# LEDA_Arcade_Controller_Mainboard_No_Spea.net
KiCad netlist of a schematic drawn in EasyEDA
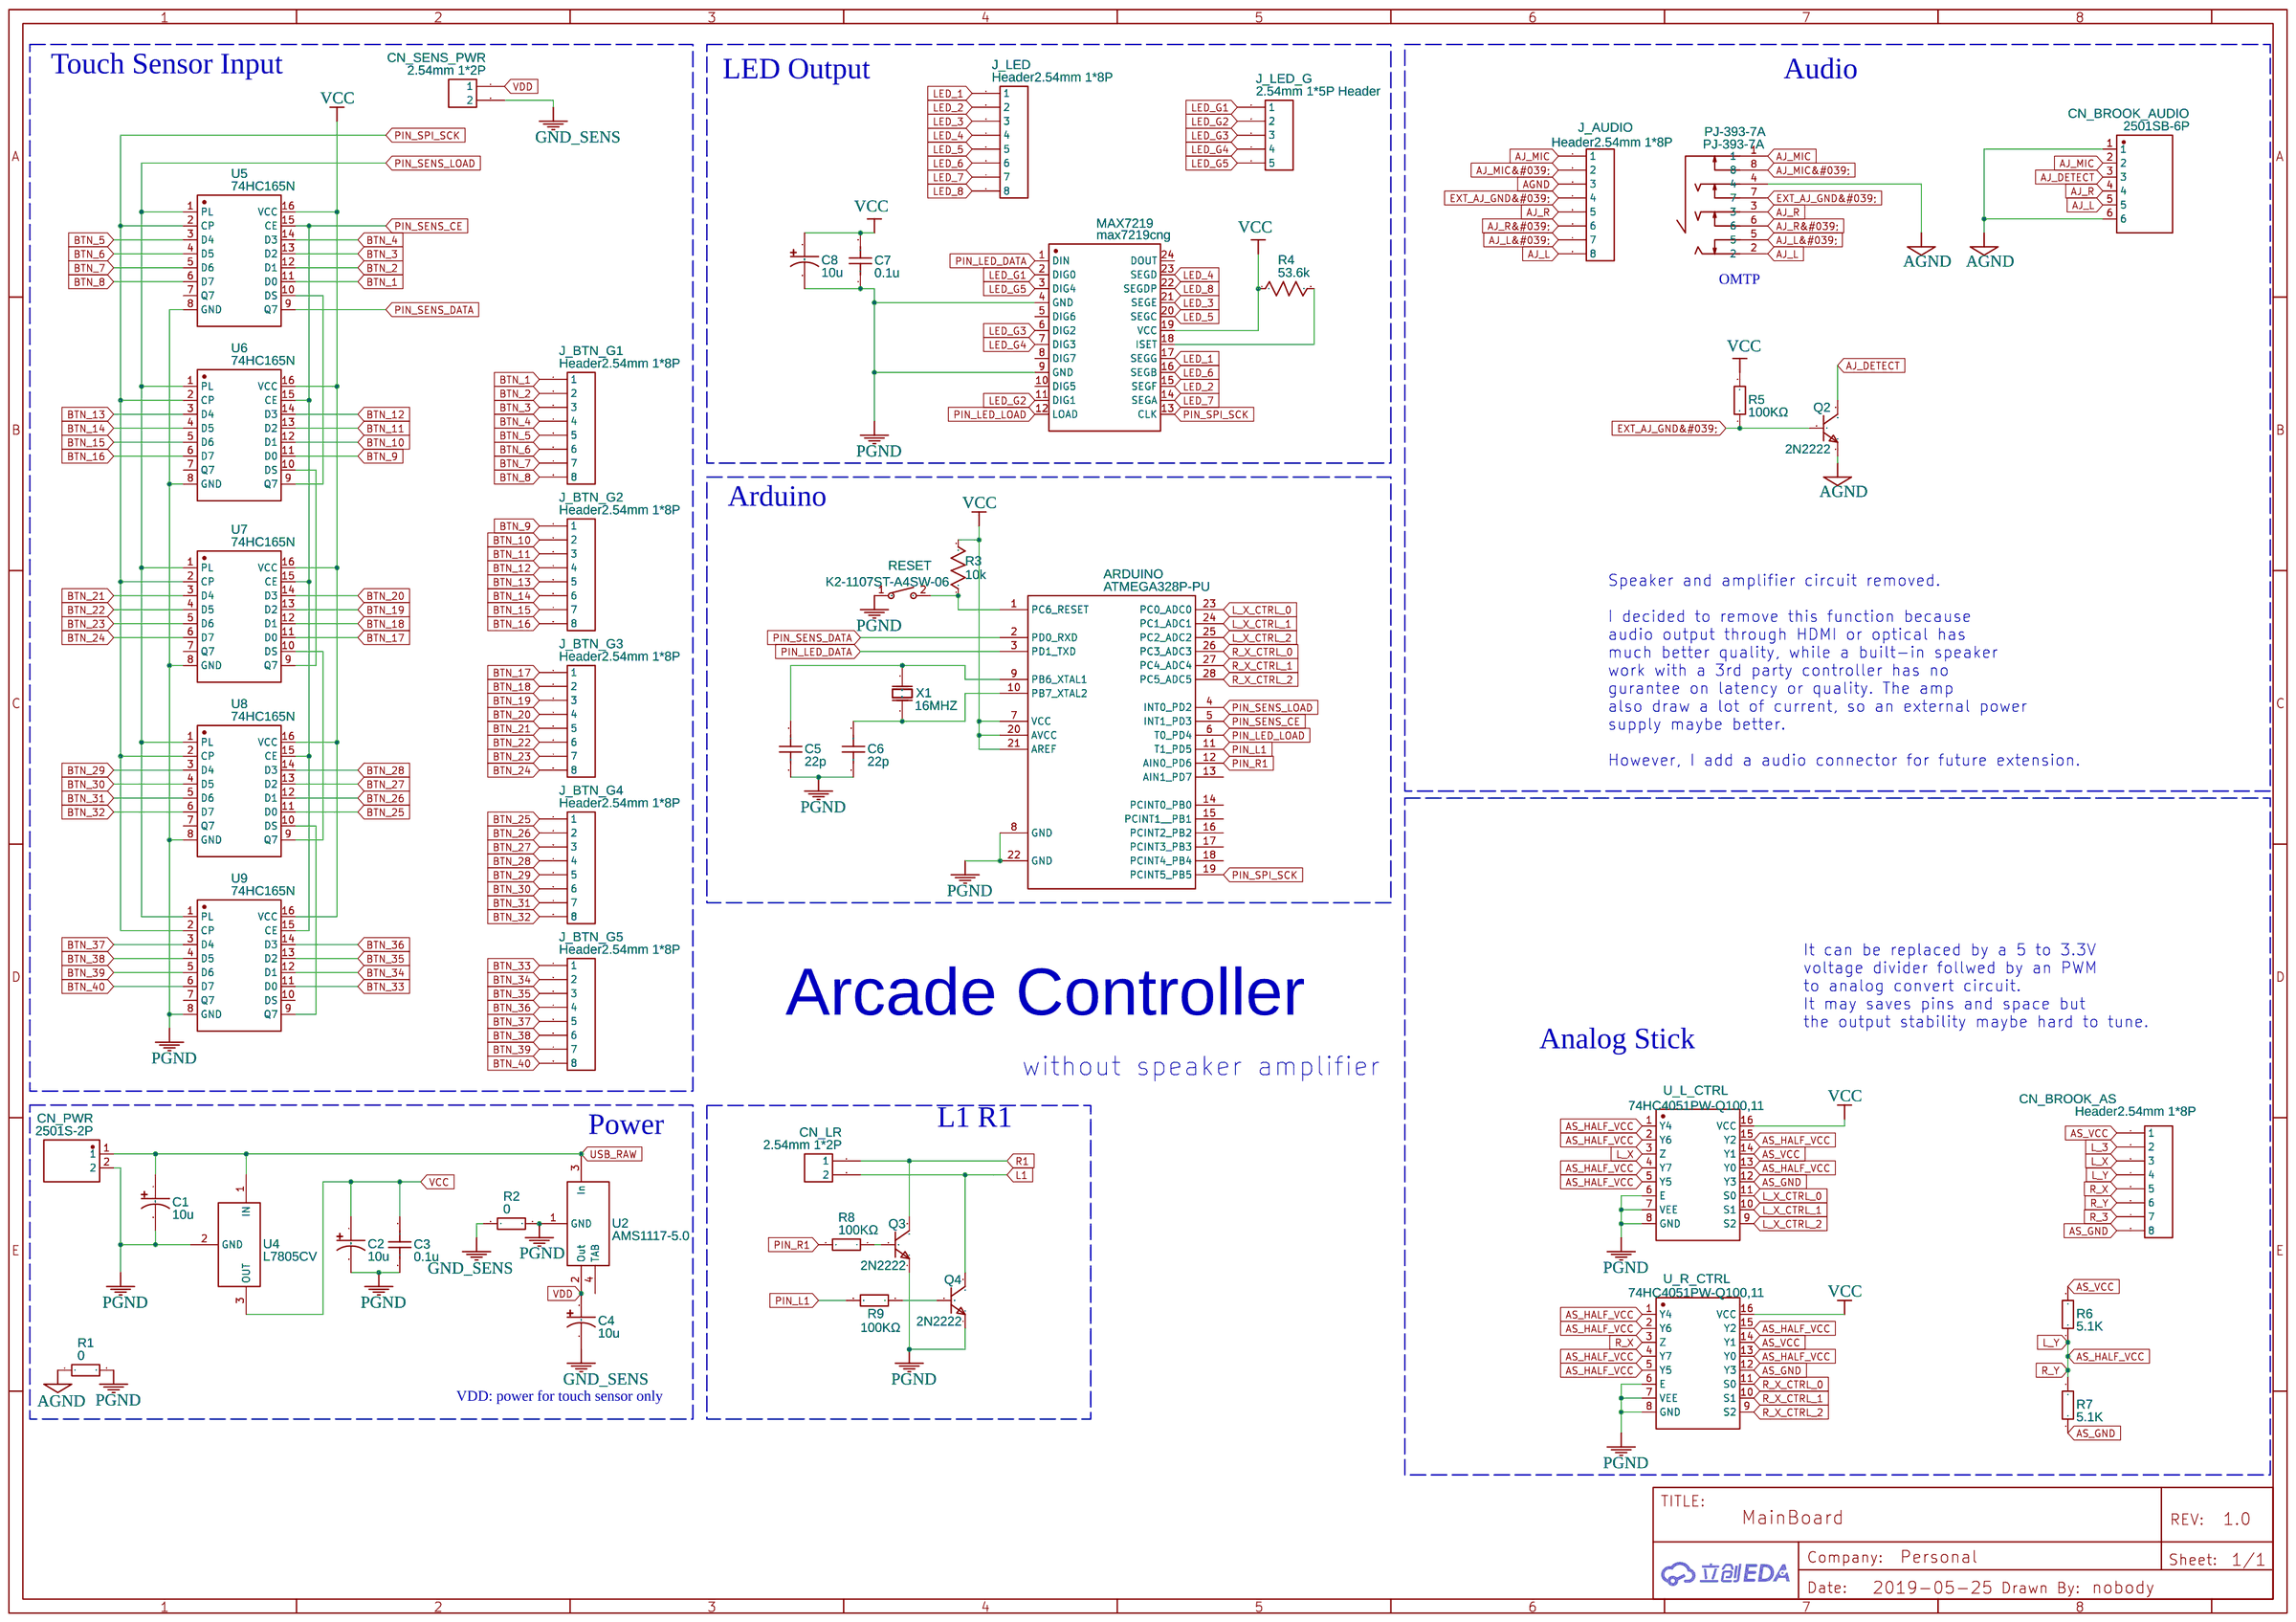
[diagram p0: schematic sheet]

(export (version "E")
  (design (tool "Eeschema 10.0.6"))
  (components
    (comp (ref "ARDUINO")
      (value "ATMEGA328P-PU")
      (fields (field (name "BOM_Supplier Part") "C33901"))
      (libsource (lib "") (part "Unknown_790_525"))
    )
    (comp (ref "C1")
      (value "10u")
      (fields (field (name "BOM_Manufacturer Part") "?"))
      (libsource (lib "") (part "Cap_Electrolytic(TH)_D4.0XF1.5_US_1"))
    )
    (comp (ref "C2")
      (value "10u")
      (fields (field (name "BOM_Manufacturer Part") "?"))
      (libsource (lib "") (part "Cap_Electrolytic(TH)_D4.0XF1.5_US_1"))
    )
    (comp (ref "C3")
      (value "0.1u")
      (fields (field (name "BOM_Manufacturer Part") "?"))
      (libsource (lib "") (part "Cap_RAD-0.2_US"))
    )
    (comp (ref "C4")
      (value "10u")
      (fields (field (name "BOM_Manufacturer Part") "?"))
      (libsource (lib "") (part "Cap_Electrolytic(TH)_D4.0XF1.5_US_2"))
    )
    (comp (ref "C5")
      (value "22p")
      (fields (field (name "BOM_Manufacturer Part") "?"))
      (libsource (lib "") (part "Cap_0603_US"))
    )
    (comp (ref "C6")
      (value "22p")
      (fields (field (name "BOM_Manufacturer Part") "?"))
      (libsource (lib "") (part "Cap_0603_US"))
    )
    (comp (ref "C7")
      (value "0.1u")
      (fields (field (name "BOM_Manufacturer Part") "?"))
      (libsource (lib "") (part "Cap_RAD-0.2_US"))
    )
    (comp (ref "C8")
      (value "10u")
      (fields (field (name "BOM_Manufacturer Part") "?"))
      (libsource (lib "") (part "Cap_Electrolytic(TH)_D4.0XF1.5_US"))
    )
    (comp (ref "CN_BROOK_AS")
      (value "Header2.54mm 1*8P")
      (fields (field (name "BOM_Supplier Part") "C49256"))
      (libsource (lib "") (part "Unknown_1530_840"))
    )
    (comp (ref "CN_BROOK_AUDIO")
      (value "2501SB-6P")
      (fields (field (name "BOM_Supplier Part") "C132455"))
      (libsource (lib "") (part "Unknown_1525_125"))
    )
    (comp (ref "CN_LR")
      (value "2.54mm 1*2P")
      (fields (field (name "BOM_Supplier Part") "C36717"))
      (libsource (lib "") (part "Unknown_590_830"))
    )
    (comp (ref "CN_PWR")
      (value "2501S-2P")
      (fields (field (name "BOM_Supplier Part") "C168996"))
      (libsource (lib "") (part "Unknown_50_825"))
    )
    (comp (ref "CN_SENS_PWR")
      (value "2.54mm 1*2P")
      (fields (field (name "BOM_Supplier Part") "C36717"))
      (libsource (lib "") (part "Unknown_335_60"))
    )
    (comp (ref "J_AUDIO")
      (value "Header2.54mm 1*8P")
      (fields (field (name "BOM_Supplier Part") "C49256"))
      (libsource (lib "") (part "Unknown_1130_145"))
    )
    (comp (ref "J_BTN_G1")
      (value "Header2.54mm 1*8P")
      (fields (field (name "BOM_Supplier Part") "C49256"))
      (libsource (lib "") (part "Unknown_400_305"))
    )
    (comp (ref "J_BTN_G2")
      (value "Header2.54mm 1*8P")
      (fields (field (name "BOM_Supplier Part") "C49256"))
      (libsource (lib "") (part "Unknown_400_410"))
    )
    (comp (ref "J_BTN_G3")
      (value "Header2.54mm 1*8P")
      (fields (field (name "BOM_Supplier Part") "C49256"))
      (libsource (lib "") (part "Unknown_400_515"))
    )
    (comp (ref "J_BTN_G4")
      (value "Header2.54mm 1*8P")
      (fields (field (name "BOM_Supplier Part") "C49256"))
      (libsource (lib "") (part "Unknown_400_620"))
    )
    (comp (ref "J_BTN_G5")
      (value "Header2.54mm 1*8P")
      (fields (field (name "BOM_Supplier Part") "C49256"))
      (libsource (lib "") (part "Unknown_400_725"))
    )
    (comp (ref "J_LED")
      (value "Header2.54mm 1*8P")
      (fields (field (name "BOM_Supplier Part") "C49256"))
      (libsource (lib "") (part "Unknown_710_100"))
    )
    (comp (ref "J_LED_G")
      (value "2.54mm 1*5P Header")
      (fields (field (name "BOM_Supplier Part") "C50951"))
      (libsource (lib "") (part "Unknown_900_90"))
    )
    (comp (ref "MAX7219")
      (value "max7219cng")
      (fields (field (name "BOM_Supplier Part") "C29160"))
      (libsource (lib "") (part "Unknown_785_235"))
    )
    (comp (ref "PJ-393-7A")
      (value "PJ-393-7A")
      (fields (field (name "BOM_Supplier Part") "C128990"))
      (libsource (lib "") (part "Unknown_1230_140"))
    )
    (comp (ref "Q2")
      (value "2N2222")
      (fields (field (name "BOM_Supplier Part") "C118536"))
      (libsource (lib "") (part "Unknown_1300_300"))
    )
    (comp (ref "Q3")
      (value "2N2222")
      (fields (field (name "BOM_Supplier Part") "C118536"))
      (libsource (lib "") (part "Unknown_635_885"))
    )
    (comp (ref "Q4")
      (value "2N2222")
      (fields (field (name "BOM_Supplier Part") "C118536"))
      (libsource (lib "") (part "Unknown_675_925"))
    )
    (comp (ref "R1")
      (value "0")
      (fields (field (name "BOM_Supplier Part") "C119982"))
      (libsource (lib "") (part "CF1/4W-0Ω±5% T52"))
    )
    (comp (ref "R2")
      (value "0")
      (fields (field (name "BOM_Supplier Part") "C119982"))
      (libsource (lib "") (part "CF1/4W-0Ω±5% T52"))
    )
    (comp (ref "R3")
      (value "10k")
      (fields (field (name "BOM_Manufacturer Part") "?"))
      (libsource (lib "") (part "Res_0603(1/10W)_US_1"))
    )
    (comp (ref "R4")
      (value "53.6k")
      (fields (field (name "BOM_Manufacturer Part") "?"))
      (libsource (lib "") (part "Res_0603(1/10W)_US"))
    )
    (comp (ref "R5")
      (value "100KΩ")
      (fields
        (field (name "BOM_Manufacturer Part") "MFR0W4F1002A50")
        (field (name "BOM_Supplier Part") "C57436")
      )
      (libsource (lib "") (part "MFR0W4F1002A50"))
    )
    (comp (ref "R6")
      (value "5.1K")
      (fields (field (name "BOM_Supplier Part") "C119340"))
      (libsource (lib "") (part "MF1/4W-5.1KΩ±1% T52"))
    )
    (comp (ref "R7")
      (value "5.1K")
      (fields (field (name "BOM_Supplier Part") "C119340"))
      (libsource (lib "") (part "MF1/4W-5.1KΩ±1% T52"))
    )
    (comp (ref "R8")
      (value "100KΩ")
      (fields
        (field (name "BOM_Manufacturer Part") "MFR0W4F1002A50")
        (field (name "BOM_Supplier Part") "C57436")
      )
      (libsource (lib "") (part "MFR0W4F1002A50_1"))
    )
    (comp (ref "R9")
      (value "100KΩ")
      (fields
        (field (name "BOM_Manufacturer Part") "MFR0W4F1002A50")
        (field (name "BOM_Supplier Part") "C57436")
      )
      (libsource (lib "") (part "MFR0W4F1002A50_1"))
    )
    (comp (ref "RESET")
      (value "K2-1107ST-A4SW-06")
      (fields (field (name "BOM_Supplier Part") "C118141"))
      (libsource (lib "") (part "Unknown_640_415"))
    )
    (comp (ref "U2")
      (value "AMS1117-5.0")
      (fields (field (name "BOM_Supplier Part") "C6187"))
      (libsource (lib "") (part "Unknown_405_870"))
    )
    (comp (ref "U4")
      (value "L7805CV")
      (fields (field (name "BOM_Supplier Part") "C111887"))
      (libsource (lib "") (part "Unknown_155_885"))
    )
    (comp (ref "U5")
      (value "74HC165N")
      (fields (field (name "BOM_Manufacturer Part") "?"))
      (libsource (lib "") (part "Unknown_165_180"))
    )
    (comp (ref "U6")
      (value "74HC165N")
      (fields (field (name "BOM_Manufacturer Part") "?"))
      (libsource (lib "") (part "Unknown_165_305"))
    )
    (comp (ref "U7")
      (value "74HC165N")
      (fields (field (name "BOM_Manufacturer Part") "?"))
      (libsource (lib "") (part "Unknown_165_435"))
    )
    (comp (ref "U8")
      (value "74HC165N")
      (fields (field (name "BOM_Manufacturer Part") "?"))
      (libsource (lib "") (part "Unknown_165_560"))
    )
    (comp (ref "U9")
      (value "74HC165N")
      (fields (field (name "BOM_Manufacturer Part") "?"))
      (libsource (lib "") (part "Unknown_165_685"))
    )
    (comp (ref "U_L_CTRL")
      (value "74HC4051PW-Q100,11")
      (fields (field (name "BOM_Supplier Part") "C179325"))
      (libsource (lib "") (part "Unknown_1210_835"))
    )
    (comp (ref "U_R_CTRL")
      (value "74HC4051PW-Q100,11")
      (fields (field (name "BOM_Supplier Part") "C179325"))
      (libsource (lib "") (part "Unknown_1210_970"))
    )
    (comp (ref "X1")
      (value "16MHZ")
      (fields
        (field (name "BOM_Manufacturer Part") "X49SD16MSD2SI")
        (field (name "BOM_Supplier Part") "C188201")
      )
      (libsource (lib "") (part "X49SD16MSD2SI"))
    )
  )
  (nets
    (net (code "1") (name "AGND") (class "Default")
      (node (ref "CN_BROOK_AUDIO") (pin "1") (pinfunction "1_1") (pintype "unspecified"))
      (node (ref "CN_BROOK_AUDIO") (pin "6") (pinfunction "6_6") (pintype "unspecified"))
      (node (ref "J_AUDIO") (pin "3") (pinfunction "3_3") (pintype "input"))
      (node (ref "PJ-393-7A") (pin "4") (pinfunction "4_4") (pintype "unspecified"))
      (node (ref "Q2") (pin "1") (pinfunction "E_1") (pintype "unspecified"))
      (node (ref "R1") (pin "1") (pinfunction "1_1") (pintype "unspecified"))
    )
    (net (code "2") (name "AJ_DETECT") (class "Default")
      (node (ref "CN_BROOK_AUDIO") (pin "3") (pinfunction "3_3") (pintype "unspecified"))
      (node (ref "Q2") (pin "3") (pinfunction "C_3") (pintype "unspecified"))
    )
    (net (code "3") (name "AJ_L") (class "Default")
      (node (ref "CN_BROOK_AUDIO") (pin "5") (pinfunction "5_5") (pintype "unspecified"))
      (node (ref "J_AUDIO") (pin "8") (pinfunction "8_8") (pintype "input"))
      (node (ref "PJ-393-7A") (pin "2") (pinfunction "2_2") (pintype "unspecified"))
    )
    (net (code "4") (name "AJ_L&#039;") (class "Default")
      (node (ref "J_AUDIO") (pin "7") (pinfunction "7_7") (pintype "input"))
      (node (ref "PJ-393-7A") (pin "5") (pinfunction "5_5") (pintype "unspecified"))
    )
    (net (code "5") (name "AJ_MIC") (class "Default")
      (node (ref "CN_BROOK_AUDIO") (pin "2") (pinfunction "2_2") (pintype "unspecified"))
      (node (ref "J_AUDIO") (pin "1") (pinfunction "1_1") (pintype "input"))
      (node (ref "PJ-393-7A") (pin "1") (pinfunction "1_1") (pintype "unspecified"))
    )
    (net (code "6") (name "AJ_MIC&#039;") (class "Default")
      (node (ref "J_AUDIO") (pin "2") (pinfunction "2_2") (pintype "input"))
      (node (ref "PJ-393-7A") (pin "8") (pinfunction "8_8") (pintype "unspecified"))
    )
    (net (code "7") (name "AJ_R") (class "Default")
      (node (ref "CN_BROOK_AUDIO") (pin "4") (pinfunction "4_4") (pintype "unspecified"))
      (node (ref "J_AUDIO") (pin "5") (pinfunction "5_5") (pintype "input"))
      (node (ref "PJ-393-7A") (pin "3") (pinfunction "3_3") (pintype "unspecified"))
    )
    (net (code "8") (name "AJ_R&#039;") (class "Default")
      (node (ref "J_AUDIO") (pin "6") (pinfunction "6_6") (pintype "input"))
      (node (ref "PJ-393-7A") (pin "6") (pinfunction "6_6") (pintype "unspecified"))
    )
    (net (code "9") (name "AS_GND") (class "Default")
      (node (ref "CN_BROOK_AS") (pin "8") (pinfunction "8_8") (pintype "input"))
      (node (ref "R7") (pin "1") (pinfunction "1_1") (pintype "unspecified"))
      (node (ref "U_L_CTRL") (pin "12") (pinfunction "Y3_12") (pintype "unspecified"))
      (node (ref "U_R_CTRL") (pin "12") (pinfunction "Y3_12") (pintype "unspecified"))
    )
    (net (code "10") (name "AS_HALF_VCC") (class "Default")
      (node (ref "CN_BROOK_AS") (pin "4") (pinfunction "4_4") (pintype "input"))
      (node (ref "CN_BROOK_AS") (pin "6") (pinfunction "6_6") (pintype "input"))
      (node (ref "R6") (pin "1") (pinfunction "1_1") (pintype "unspecified"))
      (node (ref "R7") (pin "2") (pinfunction "2_2") (pintype "unspecified"))
      (node (ref "U_L_CTRL") (pin "1") (pinfunction "Y4_1") (pintype "unspecified"))
      (node (ref "U_L_CTRL") (pin "13") (pinfunction "Y0_13") (pintype "unspecified"))
      (node (ref "U_L_CTRL") (pin "15") (pinfunction "Y2_15") (pintype "unspecified"))
      (node (ref "U_L_CTRL") (pin "2") (pinfunction "Y6_2") (pintype "unspecified"))
      (node (ref "U_L_CTRL") (pin "4") (pinfunction "Y7_4") (pintype "unspecified"))
      (node (ref "U_L_CTRL") (pin "5") (pinfunction "Y5_5") (pintype "unspecified"))
      (node (ref "U_R_CTRL") (pin "1") (pinfunction "Y4_1") (pintype "unspecified"))
      (node (ref "U_R_CTRL") (pin "13") (pinfunction "Y0_13") (pintype "unspecified"))
      (node (ref "U_R_CTRL") (pin "15") (pinfunction "Y2_15") (pintype "unspecified"))
      (node (ref "U_R_CTRL") (pin "2") (pinfunction "Y6_2") (pintype "unspecified"))
      (node (ref "U_R_CTRL") (pin "4") (pinfunction "Y7_4") (pintype "unspecified"))
      (node (ref "U_R_CTRL") (pin "5") (pinfunction "Y5_5") (pintype "unspecified"))
    )
    (net (code "11") (name "AS_VCC") (class "Default")
      (node (ref "CN_BROOK_AS") (pin "1") (pinfunction "1_1") (pintype "input"))
      (node (ref "R6") (pin "2") (pinfunction "2_2") (pintype "unspecified"))
      (node (ref "U_L_CTRL") (pin "14") (pinfunction "Y1_14") (pintype "unspecified"))
      (node (ref "U_R_CTRL") (pin "14") (pinfunction "Y1_14") (pintype "unspecified"))
    )
    (net (code "12") (name "BTN_1") (class "Default")
      (node (ref "J_BTN_G1") (pin "1") (pinfunction "1_1") (pintype "input"))
      (node (ref "U5") (pin "11") (pinfunction "D0_11") (pintype "unspecified"))
    )
    (net (code "13") (name "BTN_2") (class "Default")
      (node (ref "J_BTN_G1") (pin "2") (pinfunction "2_2") (pintype "input"))
      (node (ref "U5") (pin "12") (pinfunction "D1_12") (pintype "unspecified"))
    )
    (net (code "14") (name "BTN_3") (class "Default")
      (node (ref "J_BTN_G1") (pin "3") (pinfunction "3_3") (pintype "input"))
      (node (ref "U5") (pin "13") (pinfunction "D2_13") (pintype "unspecified"))
    )
    (net (code "15") (name "BTN_4") (class "Default")
      (node (ref "J_BTN_G1") (pin "4") (pinfunction "4_4") (pintype "input"))
      (node (ref "U5") (pin "14") (pinfunction "D3_14") (pintype "unspecified"))
    )
    (net (code "16") (name "BTN_5") (class "Default")
      (node (ref "J_BTN_G1") (pin "5") (pinfunction "5_5") (pintype "input"))
      (node (ref "U5") (pin "3") (pinfunction "D4_3") (pintype "unspecified"))
    )
    (net (code "17") (name "BTN_6") (class "Default")
      (node (ref "J_BTN_G1") (pin "6") (pinfunction "6_6") (pintype "input"))
      (node (ref "U5") (pin "4") (pinfunction "D5_4") (pintype "unspecified"))
    )
    (net (code "18") (name "BTN_7") (class "Default")
      (node (ref "J_BTN_G1") (pin "7") (pinfunction "7_7") (pintype "input"))
      (node (ref "U5") (pin "5") (pinfunction "D6_5") (pintype "unspecified"))
    )
    (net (code "19") (name "BTN_8") (class "Default")
      (node (ref "J_BTN_G1") (pin "8") (pinfunction "8_8") (pintype "input"))
      (node (ref "U5") (pin "6") (pinfunction "D7_6") (pintype "unspecified"))
    )
    (net (code "20") (name "BTN_9") (class "Default")
      (node (ref "J_BTN_G2") (pin "1") (pinfunction "1_1") (pintype "input"))
      (node (ref "U6") (pin "11") (pinfunction "D0_11") (pintype "unspecified"))
    )
    (net (code "21") (name "BTN_10") (class "Default")
      (node (ref "J_BTN_G2") (pin "2") (pinfunction "2_2") (pintype "input"))
      (node (ref "U6") (pin "12") (pinfunction "D1_12") (pintype "unspecified"))
    )
    (net (code "22") (name "BTN_11") (class "Default")
      (node (ref "J_BTN_G2") (pin "3") (pinfunction "3_3") (pintype "input"))
      (node (ref "U6") (pin "13") (pinfunction "D2_13") (pintype "unspecified"))
    )
    (net (code "23") (name "BTN_12") (class "Default")
      (node (ref "J_BTN_G2") (pin "4") (pinfunction "4_4") (pintype "input"))
      (node (ref "U6") (pin "14") (pinfunction "D3_14") (pintype "unspecified"))
    )
    (net (code "24") (name "BTN_13") (class "Default")
      (node (ref "J_BTN_G2") (pin "5") (pinfunction "5_5") (pintype "input"))
      (node (ref "U6") (pin "3") (pinfunction "D4_3") (pintype "unspecified"))
    )
    (net (code "25") (name "BTN_14") (class "Default")
      (node (ref "J_BTN_G2") (pin "6") (pinfunction "6_6") (pintype "input"))
      (node (ref "U6") (pin "4") (pinfunction "D5_4") (pintype "unspecified"))
    )
    (net (code "26") (name "BTN_15") (class "Default")
      (node (ref "J_BTN_G2") (pin "7") (pinfunction "7_7") (pintype "input"))
      (node (ref "U6") (pin "5") (pinfunction "D6_5") (pintype "unspecified"))
    )
    (net (code "27") (name "BTN_16") (class "Default")
      (node (ref "J_BTN_G2") (pin "8") (pinfunction "8_8") (pintype "input"))
      (node (ref "U6") (pin "6") (pinfunction "D7_6") (pintype "unspecified"))
    )
    (net (code "28") (name "BTN_17") (class "Default")
      (node (ref "J_BTN_G3") (pin "1") (pinfunction "1_1") (pintype "input"))
      (node (ref "U7") (pin "11") (pinfunction "D0_11") (pintype "unspecified"))
    )
    (net (code "29") (name "BTN_18") (class "Default")
      (node (ref "J_BTN_G3") (pin "2") (pinfunction "2_2") (pintype "input"))
      (node (ref "U7") (pin "12") (pinfunction "D1_12") (pintype "unspecified"))
    )
    (net (code "30") (name "BTN_19") (class "Default")
      (node (ref "J_BTN_G3") (pin "3") (pinfunction "3_3") (pintype "input"))
      (node (ref "U7") (pin "13") (pinfunction "D2_13") (pintype "unspecified"))
    )
    (net (code "31") (name "BTN_20") (class "Default")
      (node (ref "J_BTN_G3") (pin "4") (pinfunction "4_4") (pintype "input"))
      (node (ref "U7") (pin "14") (pinfunction "D3_14") (pintype "unspecified"))
    )
    (net (code "32") (name "BTN_21") (class "Default")
      (node (ref "J_BTN_G3") (pin "5") (pinfunction "5_5") (pintype "input"))
      (node (ref "U7") (pin "3") (pinfunction "D4_3") (pintype "unspecified"))
    )
    (net (code "33") (name "BTN_22") (class "Default")
      (node (ref "J_BTN_G3") (pin "6") (pinfunction "6_6") (pintype "input"))
      (node (ref "U7") (pin "4") (pinfunction "D5_4") (pintype "unspecified"))
    )
    (net (code "34") (name "BTN_23") (class "Default")
      (node (ref "J_BTN_G3") (pin "7") (pinfunction "7_7") (pintype "input"))
      (node (ref "U7") (pin "5") (pinfunction "D6_5") (pintype "unspecified"))
    )
    (net (code "35") (name "BTN_24") (class "Default")
      (node (ref "J_BTN_G3") (pin "8") (pinfunction "8_8") (pintype "input"))
      (node (ref "U7") (pin "6") (pinfunction "D7_6") (pintype "unspecified"))
    )
    (net (code "36") (name "BTN_25") (class "Default")
      (node (ref "J_BTN_G4") (pin "1") (pinfunction "1_1") (pintype "input"))
      (node (ref "U8") (pin "11") (pinfunction "D0_11") (pintype "unspecified"))
    )
    (net (code "37") (name "BTN_26") (class "Default")
      (node (ref "J_BTN_G4") (pin "2") (pinfunction "2_2") (pintype "input"))
      (node (ref "U8") (pin "12") (pinfunction "D1_12") (pintype "unspecified"))
    )
    (net (code "38") (name "BTN_27") (class "Default")
      (node (ref "J_BTN_G4") (pin "3") (pinfunction "3_3") (pintype "input"))
      (node (ref "U8") (pin "13") (pinfunction "D2_13") (pintype "unspecified"))
    )
    (net (code "39") (name "BTN_28") (class "Default")
      (node (ref "J_BTN_G4") (pin "4") (pinfunction "4_4") (pintype "input"))
      (node (ref "U8") (pin "14") (pinfunction "D3_14") (pintype "unspecified"))
    )
    (net (code "40") (name "BTN_29") (class "Default")
      (node (ref "J_BTN_G4") (pin "5") (pinfunction "5_5") (pintype "input"))
      (node (ref "U8") (pin "3") (pinfunction "D4_3") (pintype "unspecified"))
    )
    (net (code "41") (name "BTN_30") (class "Default")
      (node (ref "J_BTN_G4") (pin "6") (pinfunction "6_6") (pintype "input"))
      (node (ref "U8") (pin "4") (pinfunction "D5_4") (pintype "unspecified"))
    )
    (net (code "42") (name "BTN_31") (class "Default")
      (node (ref "J_BTN_G4") (pin "7") (pinfunction "7_7") (pintype "input"))
      (node (ref "U8") (pin "5") (pinfunction "D6_5") (pintype "unspecified"))
    )
    (net (code "43") (name "BTN_32") (class "Default")
      (node (ref "J_BTN_G4") (pin "8") (pinfunction "8_8") (pintype "input"))
      (node (ref "U8") (pin "6") (pinfunction "D7_6") (pintype "unspecified"))
    )
    (net (code "44") (name "BTN_33") (class "Default")
      (node (ref "J_BTN_G5") (pin "1") (pinfunction "1_1") (pintype "input"))
      (node (ref "U9") (pin "11") (pinfunction "D0_11") (pintype "unspecified"))
    )
    (net (code "45") (name "BTN_34") (class "Default")
      (node (ref "J_BTN_G5") (pin "2") (pinfunction "2_2") (pintype "input"))
      (node (ref "U9") (pin "12") (pinfunction "D1_12") (pintype "unspecified"))
    )
    (net (code "46") (name "BTN_35") (class "Default")
      (node (ref "J_BTN_G5") (pin "3") (pinfunction "3_3") (pintype "input"))
      (node (ref "U9") (pin "13") (pinfunction "D2_13") (pintype "unspecified"))
    )
    (net (code "47") (name "BTN_36") (class "Default")
      (node (ref "J_BTN_G5") (pin "4") (pinfunction "4_4") (pintype "input"))
      (node (ref "U9") (pin "14") (pinfunction "D3_14") (pintype "unspecified"))
    )
    (net (code "48") (name "BTN_37") (class "Default")
      (node (ref "J_BTN_G5") (pin "5") (pinfunction "5_5") (pintype "input"))
      (node (ref "U9") (pin "3") (pinfunction "D4_3") (pintype "unspecified"))
    )
    (net (code "49") (name "BTN_38") (class "Default")
      (node (ref "J_BTN_G5") (pin "6") (pinfunction "6_6") (pintype "input"))
      (node (ref "U9") (pin "4") (pinfunction "D5_4") (pintype "unspecified"))
    )
    (net (code "50") (name "BTN_39") (class "Default")
      (node (ref "J_BTN_G5") (pin "7") (pinfunction "7_7") (pintype "input"))
      (node (ref "U9") (pin "5") (pinfunction "D6_5") (pintype "unspecified"))
    )
    (net (code "51") (name "BTN_40") (class "Default")
      (node (ref "J_BTN_G5") (pin "8") (pinfunction "8_8") (pintype "input"))
      (node (ref "U9") (pin "6") (pinfunction "D7_6") (pintype "unspecified"))
    )
    (net (code "52") (name "EXT_AJ_GND&#039;") (class "Default")
      (node (ref "J_AUDIO") (pin "4") (pinfunction "4_4") (pintype "input"))
      (node (ref "PJ-393-7A") (pin "7") (pinfunction "7_7") (pintype "unspecified"))
      (node (ref "Q2") (pin "2") (pinfunction "B_2") (pintype "unspecified"))
      (node (ref "R5") (pin "1") (pinfunction "1_1") (pintype "input"))
    )
    (net (code "53") (name "GND_SENS") (class "Default")
      (node (ref "C4") (pin "2") (pinfunction "2_2") (pintype "unspecified"))
      (node (ref "CN_SENS_PWR") (pin "2") (pinfunction "2_2") (pintype "input"))
      (node (ref "R2") (pin "1") (pinfunction "1_1") (pintype "unspecified"))
    )
    (net (code "54") (name "L1") (class "Default")
      (node (ref "CN_LR") (pin "2") (pinfunction "2_2") (pintype "input"))
      (node (ref "Q4") (pin "3") (pinfunction "C_3") (pintype "unspecified"))
    )
    (net (code "55") (name "LED_1") (class "Default")
      (node (ref "J_LED") (pin "1") (pinfunction "1_1") (pintype "input"))
      (node (ref "MAX7219") (pin "17") (pinfunction "SEGG_17") (pintype "unspecified"))
    )
    (net (code "56") (name "LED_2") (class "Default")
      (node (ref "J_LED") (pin "2") (pinfunction "2_2") (pintype "input"))
      (node (ref "MAX7219") (pin "15") (pinfunction "SEGF_15") (pintype "unspecified"))
    )
    (net (code "57") (name "LED_3") (class "Default")
      (node (ref "J_LED") (pin "3") (pinfunction "3_3") (pintype "input"))
      (node (ref "MAX7219") (pin "21") (pinfunction "SEGE_21") (pintype "unspecified"))
    )
    (net (code "58") (name "LED_4") (class "Default")
      (node (ref "J_LED") (pin "4") (pinfunction "4_4") (pintype "input"))
      (node (ref "MAX7219") (pin "23") (pinfunction "SEGD_23") (pintype "unspecified"))
    )
    (net (code "59") (name "LED_5") (class "Default")
      (node (ref "J_LED") (pin "5") (pinfunction "5_5") (pintype "input"))
      (node (ref "MAX7219") (pin "20") (pinfunction "SEGC_20") (pintype "unspecified"))
    )
    (net (code "60") (name "LED_6") (class "Default")
      (node (ref "J_LED") (pin "6") (pinfunction "6_6") (pintype "input"))
      (node (ref "MAX7219") (pin "16") (pinfunction "SEGB_16") (pintype "unspecified"))
    )
    (net (code "61") (name "LED_7") (class "Default")
      (node (ref "J_LED") (pin "7") (pinfunction "7_7") (pintype "input"))
      (node (ref "MAX7219") (pin "14") (pinfunction "SEGA_14") (pintype "unspecified"))
    )
    (net (code "62") (name "LED_8") (class "Default")
      (node (ref "J_LED") (pin "8") (pinfunction "8_8") (pintype "input"))
      (node (ref "MAX7219") (pin "22") (pinfunction "SEGDP_22") (pintype "unspecified"))
    )
    (net (code "63") (name "LED_G1") (class "Default")
      (node (ref "J_LED_G") (pin "1") (pinfunction "1_1") (pintype "input"))
      (node (ref "MAX7219") (pin "2") (pinfunction "DIG0_2") (pintype "unspecified"))
    )
    (net (code "64") (name "LED_G2") (class "Default")
      (node (ref "J_LED_G") (pin "2") (pinfunction "2_2") (pintype "input"))
      (node (ref "MAX7219") (pin "11") (pinfunction "DIG1_11") (pintype "unspecified"))
    )
    (net (code "65") (name "LED_G3") (class "Default")
      (node (ref "J_LED_G") (pin "3") (pinfunction "3_3") (pintype "input"))
      (node (ref "MAX7219") (pin "6") (pinfunction "DIG2_6") (pintype "unspecified"))
    )
    (net (code "66") (name "LED_G4") (class "Default")
      (node (ref "J_LED_G") (pin "4") (pinfunction "4_4") (pintype "input"))
      (node (ref "MAX7219") (pin "7") (pinfunction "DIG3_7") (pintype "unspecified"))
    )
    (net (code "67") (name "LED_G5") (class "Default")
      (node (ref "J_LED_G") (pin "5") (pinfunction "5_5") (pintype "input"))
      (node (ref "MAX7219") (pin "3") (pinfunction "DIG4_3") (pintype "unspecified"))
    )
    (net (code "68") (name "L_3") (class "Default")
      (node (ref "CN_BROOK_AS") (pin "2") (pinfunction "2_2") (pintype "input"))
    )
    (net (code "69") (name "L_X") (class "Default")
      (node (ref "CN_BROOK_AS") (pin "3") (pinfunction "3_3") (pintype "input"))
      (node (ref "U_L_CTRL") (pin "3") (pinfunction "Z_3") (pintype "unspecified"))
    )
    (net (code "70") (name "L_X_CTRL_0") (class "Default")
      (node (ref "ARDUINO") (pin "23") (pinfunction "PC0_ADC0_23") (pintype "bidirectional"))
      (node (ref "U_L_CTRL") (pin "11") (pinfunction "S0_11") (pintype "unspecified"))
    )
    (net (code "71") (name "L_X_CTRL_1") (class "Default")
      (node (ref "ARDUINO") (pin "24") (pinfunction "PC1_ADC1_24") (pintype "bidirectional"))
      (node (ref "U_L_CTRL") (pin "10") (pinfunction "S1_10") (pintype "unspecified"))
    )
    (net (code "72") (name "L_X_CTRL_2") (class "Default")
      (node (ref "ARDUINO") (pin "25") (pinfunction "PC2_ADC2_25") (pintype "bidirectional"))
      (node (ref "U_L_CTRL") (pin "9") (pinfunction "S2_9") (pintype "unspecified"))
    )
    (net (code "73") (name "Net-(ARDUINO-PB6_XTAL1)") (class "Default")
      (node (ref "ARDUINO") (pin "9") (pinfunction "PB6_XTAL1_9") (pintype "bidirectional"))
      (node (ref "C5") (pin "2") (pinfunction "2_2") (pintype "unspecified"))
      (node (ref "X1") (pin "1") (pinfunction "OSC1_1") (pintype "input"))
    )
    (net (code "74") (name "Net-(ARDUINO-PB7_XTAL2)") (class "Default")
      (node (ref "ARDUINO") (pin "10") (pinfunction "PB7_XTAL2_10") (pintype "bidirectional"))
      (node (ref "C6") (pin "2") (pinfunction "2_2") (pintype "unspecified"))
      (node (ref "X1") (pin "2") (pinfunction "OSC2_2") (pintype "input"))
    )
    (net (code "75") (name "Net-(ARDUINO-PC6_RESET)") (class "Default")
      (node (ref "ARDUINO") (pin "1") (pinfunction "PC6_RESET_1") (pintype "bidirectional"))
      (node (ref "R3") (pin "1") (pinfunction "1_1") (pintype "unspecified"))
      (node (ref "RESET") (pin "2") (pinfunction "2_2") (pintype "unspecified"))
    )
    (net (code "76") (name "Net-(MAX7219-ISET)") (class "Default")
      (node (ref "MAX7219") (pin "18") (pinfunction "ISET_18") (pintype "unspecified"))
      (node (ref "R4") (pin "2") (pinfunction "2_2") (pintype "unspecified"))
    )
    (net (code "77") (name "Net-(Q3-B)") (class "Default")
      (node (ref "Q3") (pin "2") (pinfunction "B_2") (pintype "unspecified"))
      (node (ref "R8") (pin "1") (pinfunction "1_1") (pintype "input"))
    )
    (net (code "78") (name "Net-(Q4-B)") (class "Default")
      (node (ref "Q4") (pin "2") (pinfunction "B_2") (pintype "unspecified"))
      (node (ref "R9") (pin "1") (pinfunction "1_1") (pintype "input"))
    )
    (net (code "79") (name "Net-(U5-DS)") (class "Default")
      (node (ref "U5") (pin "10") (pinfunction "DS_10") (pintype "unspecified"))
      (node (ref "U6") (pin "9") (pinfunction "Q7_9") (pintype "unspecified"))
    )
    (net (code "80") (name "Net-(U6-DS)") (class "Default")
      (node (ref "U6") (pin "10") (pinfunction "DS_10") (pintype "unspecified"))
      (node (ref "U7") (pin "9") (pinfunction "Q7_9") (pintype "unspecified"))
    )
    (net (code "81") (name "Net-(U7-DS)") (class "Default")
      (node (ref "U7") (pin "10") (pinfunction "DS_10") (pintype "unspecified"))
      (node (ref "U8") (pin "9") (pinfunction "Q7_9") (pintype "unspecified"))
    )
    (net (code "82") (name "Net-(U8-DS)") (class "Default")
      (node (ref "U8") (pin "10") (pinfunction "DS_10") (pintype "unspecified"))
      (node (ref "U9") (pin "9") (pinfunction "Q7_9") (pintype "unspecified"))
    )
    (net (code "83") (name "PGND") (class "Default")
      (node (ref "ARDUINO") (pin "22") (pinfunction "GND_22") (pintype "passive"))
      (node (ref "ARDUINO") (pin "8") (pinfunction "GND_8") (pintype "passive"))
      (node (ref "C1") (pin "2") (pinfunction "2_2") (pintype "unspecified"))
      (node (ref "C2") (pin "2") (pinfunction "2_2") (pintype "unspecified"))
      (node (ref "C3") (pin "1") (pinfunction "1_1") (pintype "unspecified"))
      (node (ref "C5") (pin "1") (pinfunction "1_1") (pintype "unspecified"))
      (node (ref "C6") (pin "1") (pinfunction "1_1") (pintype "unspecified"))
      (node (ref "C7") (pin "1") (pinfunction "1_1") (pintype "unspecified"))
      (node (ref "C8") (pin "2") (pinfunction "2_2") (pintype "unspecified"))
      (node (ref "CN_PWR") (pin "2") (pinfunction "2_2") (pintype "unspecified"))
      (node (ref "MAX7219") (pin "4") (pinfunction "GND_4") (pintype "unspecified"))
      (node (ref "MAX7219") (pin "9") (pinfunction "GND_9") (pintype "unspecified"))
      (node (ref "Q3") (pin "1") (pinfunction "E_1") (pintype "unspecified"))
      (node (ref "Q4") (pin "1") (pinfunction "E_1") (pintype "unspecified"))
      (node (ref "R1") (pin "2") (pinfunction "2_2") (pintype "unspecified"))
      (node (ref "R2") (pin "2") (pinfunction "2_2") (pintype "unspecified"))
      (node (ref "RESET") (pin "1") (pinfunction "1_1") (pintype "unspecified"))
      (node (ref "U2") (pin "1") (pinfunction "GND_1") (pintype "unspecified"))
      (node (ref "U4") (pin "2") (pinfunction "GND_2") (pintype "passive"))
      (node (ref "U5") (pin "8") (pinfunction "GND_8") (pintype "unspecified"))
      (node (ref "U6") (pin "8") (pinfunction "GND_8") (pintype "unspecified"))
      (node (ref "U7") (pin "8") (pinfunction "GND_8") (pintype "unspecified"))
      (node (ref "U8") (pin "8") (pinfunction "GND_8") (pintype "unspecified"))
      (node (ref "U9") (pin "8") (pinfunction "GND_8") (pintype "unspecified"))
      (node (ref "U_L_CTRL") (pin "6") (pinfunction "E_6") (pintype "unspecified"))
      (node (ref "U_L_CTRL") (pin "7") (pinfunction "VEE_7") (pintype "unspecified"))
      (node (ref "U_L_CTRL") (pin "8") (pinfunction "GND_8") (pintype "unspecified"))
      (node (ref "U_R_CTRL") (pin "6") (pinfunction "E_6") (pintype "unspecified"))
      (node (ref "U_R_CTRL") (pin "7") (pinfunction "VEE_7") (pintype "unspecified"))
      (node (ref "U_R_CTRL") (pin "8") (pinfunction "GND_8") (pintype "unspecified"))
    )
    (net (code "84") (name "PIN_L1") (class "Default")
      (node (ref "ARDUINO") (pin "11") (pinfunction "T1_PD5_11") (pintype "bidirectional"))
      (node (ref "R9") (pin "2") (pinfunction "2_2") (pintype "input"))
    )
    (net (code "85") (name "PIN_LED_DATA") (class "Default")
      (node (ref "ARDUINO") (pin "3") (pinfunction "PD1_TXD_3") (pintype "bidirectional"))
      (node (ref "MAX7219") (pin "1") (pinfunction "DIN_1") (pintype "unspecified"))
    )
    (net (code "86") (name "PIN_LED_LOAD") (class "Default")
      (node (ref "ARDUINO") (pin "6") (pinfunction "T0_PD4_6") (pintype "bidirectional"))
      (node (ref "MAX7219") (pin "12") (pinfunction "LOAD_12") (pintype "unspecified"))
    )
    (net (code "87") (name "PIN_R1") (class "Default")
      (node (ref "ARDUINO") (pin "12") (pinfunction "AIN0_PD6_12") (pintype "bidirectional"))
      (node (ref "R8") (pin "2") (pinfunction "2_2") (pintype "input"))
    )
    (net (code "88") (name "PIN_SENS_CE") (class "Default")
      (node (ref "ARDUINO") (pin "5") (pinfunction "INT1_PD3_5") (pintype "bidirectional"))
      (node (ref "U5") (pin "15") (pinfunction "CE_15") (pintype "unspecified"))
      (node (ref "U6") (pin "15") (pinfunction "CE_15") (pintype "unspecified"))
      (node (ref "U7") (pin "15") (pinfunction "CE_15") (pintype "unspecified"))
      (node (ref "U8") (pin "15") (pinfunction "CE_15") (pintype "unspecified"))
      (node (ref "U9") (pin "15") (pinfunction "CE_15") (pintype "unspecified"))
    )
    (net (code "89") (name "PIN_SENS_DATA") (class "Default")
      (node (ref "ARDUINO") (pin "2") (pinfunction "PD0_RXD_2") (pintype "bidirectional"))
      (node (ref "U5") (pin "9") (pinfunction "Q7_9") (pintype "unspecified"))
    )
    (net (code "90") (name "PIN_SENS_LOAD") (class "Default")
      (node (ref "ARDUINO") (pin "4") (pinfunction "INT0_PD2_4") (pintype "bidirectional"))
      (node (ref "U5") (pin "1") (pinfunction "PL_1") (pintype "unspecified"))
      (node (ref "U6") (pin "1") (pinfunction "PL_1") (pintype "unspecified"))
      (node (ref "U7") (pin "1") (pinfunction "PL_1") (pintype "unspecified"))
      (node (ref "U8") (pin "1") (pinfunction "PL_1") (pintype "unspecified"))
      (node (ref "U9") (pin "1") (pinfunction "PL_1") (pintype "unspecified"))
    )
    (net (code "91") (name "PIN_SPI_SCK") (class "Default")
      (node (ref "ARDUINO") (pin "19") (pinfunction "PCINT5_PB5_19") (pintype "bidirectional"))
      (node (ref "MAX7219") (pin "13") (pinfunction "CLK_13") (pintype "unspecified"))
      (node (ref "U5") (pin "2") (pinfunction "CP_2") (pintype "unspecified"))
      (node (ref "U6") (pin "2") (pinfunction "CP_2") (pintype "unspecified"))
      (node (ref "U7") (pin "2") (pinfunction "CP_2") (pintype "unspecified"))
      (node (ref "U8") (pin "2") (pinfunction "CP_2") (pintype "unspecified"))
      (node (ref "U9") (pin "2") (pinfunction "CP_2") (pintype "unspecified"))
    )
    (net (code "92") (name "R1") (class "Default")
      (node (ref "CN_LR") (pin "1") (pinfunction "1_1") (pintype "input"))
      (node (ref "Q3") (pin "3") (pinfunction "C_3") (pintype "unspecified"))
    )
    (net (code "93") (name "R_3") (class "Default")
      (node (ref "CN_BROOK_AS") (pin "7") (pinfunction "7_7") (pintype "input"))
    )
    (net (code "94") (name "R_X") (class "Default")
      (node (ref "CN_BROOK_AS") (pin "5") (pinfunction "5_5") (pintype "input"))
      (node (ref "U_R_CTRL") (pin "3") (pinfunction "Z_3") (pintype "unspecified"))
    )
    (net (code "95") (name "R_X_CTRL_0") (class "Default")
      (node (ref "ARDUINO") (pin "26") (pinfunction "PC3_ADC3_26") (pintype "bidirectional"))
      (node (ref "U_R_CTRL") (pin "11") (pinfunction "S0_11") (pintype "unspecified"))
    )
    (net (code "96") (name "R_X_CTRL_1") (class "Default")
      (node (ref "ARDUINO") (pin "27") (pinfunction "PC4_ADC4_27") (pintype "bidirectional"))
      (node (ref "U_R_CTRL") (pin "10") (pinfunction "S1_10") (pintype "unspecified"))
    )
    (net (code "97") (name "R_X_CTRL_2") (class "Default")
      (node (ref "ARDUINO") (pin "28") (pinfunction "PC5_ADC5_28") (pintype "bidirectional"))
      (node (ref "U_R_CTRL") (pin "9") (pinfunction "S2_9") (pintype "unspecified"))
    )
    (net (code "98") (name "USB_RAW") (class "Default")
      (node (ref "C1") (pin "1") (pinfunction "1_1") (pintype "unspecified"))
      (node (ref "CN_PWR") (pin "1") (pinfunction "1_1") (pintype "unspecified"))
      (node (ref "U2") (pin "3") (pinfunction "In_3") (pintype "unspecified"))
      (node (ref "U4") (pin "1") (pinfunction "IN_1") (pintype "passive"))
    )
    (net (code "99") (name "VCC") (class "Default")
      (node (ref "ARDUINO") (pin "20") (pinfunction "AVCC_20") (pintype "passive"))
      (node (ref "ARDUINO") (pin "21") (pinfunction "AREF_21") (pintype "passive"))
      (node (ref "ARDUINO") (pin "7") (pinfunction "VCC_7") (pintype "passive"))
      (node (ref "C2") (pin "1") (pinfunction "1_1") (pintype "unspecified"))
      (node (ref "C3") (pin "2") (pinfunction "2_2") (pintype "unspecified"))
      (node (ref "C7") (pin "2") (pinfunction "2_2") (pintype "unspecified"))
      (node (ref "C8") (pin "1") (pinfunction "1_1") (pintype "unspecified"))
      (node (ref "MAX7219") (pin "19") (pinfunction "VCC_19") (pintype "unspecified"))
      (node (ref "R3") (pin "2") (pinfunction "2_2") (pintype "unspecified"))
      (node (ref "R4") (pin "1") (pinfunction "1_1") (pintype "unspecified"))
      (node (ref "R5") (pin "2") (pinfunction "2_2") (pintype "input"))
      (node (ref "U4") (pin "3") (pinfunction "OUT_3") (pintype "passive"))
      (node (ref "U5") (pin "16") (pinfunction "VCC_16") (pintype "unspecified"))
      (node (ref "U6") (pin "16") (pinfunction "VCC_16") (pintype "unspecified"))
      (node (ref "U7") (pin "16") (pinfunction "VCC_16") (pintype "unspecified"))
      (node (ref "U8") (pin "16") (pinfunction "VCC_16") (pintype "unspecified"))
      (node (ref "U9") (pin "16") (pinfunction "VCC_16") (pintype "unspecified"))
      (node (ref "U_L_CTRL") (pin "16") (pinfunction "VCC_16") (pintype "unspecified"))
      (node (ref "U_R_CTRL") (pin "16") (pinfunction "VCC_16") (pintype "unspecified"))
    )
    (net (code "100") (name "VDD") (class "Default")
      (node (ref "C4") (pin "1") (pinfunction "1_1") (pintype "unspecified"))
      (node (ref "CN_SENS_PWR") (pin "1") (pinfunction "1_1") (pintype "input"))
      (node (ref "U2") (pin "2") (pinfunction "Out_2") (pintype "unspecified"))
    )
    (net (code "101") (name "unconnected-(ARDUINO-AIN1_PD7-Pad13)") (class "Default")
      (node (ref "ARDUINO") (pin "13") (pinfunction "AIN1_PD7_13") (pintype "bidirectional"))
    )
    (net (code "102") (name "unconnected-(ARDUINO-PCINT0_PB0-Pad14)") (class "Default")
      (node (ref "ARDUINO") (pin "14") (pinfunction "PCINT0_PB0_14") (pintype "bidirectional"))
    )
    (net (code "103") (name "unconnected-(ARDUINO-PCINT1__PB1-Pad15)") (class "Default")
      (node (ref "ARDUINO") (pin "15") (pinfunction "PCINT1__PB1_15") (pintype "bidirectional"))
    )
    (net (code "104") (name "unconnected-(ARDUINO-PCINT2_PB2-Pad16)") (class "Default")
      (node (ref "ARDUINO") (pin "16") (pinfunction "PCINT2_PB2_16") (pintype "bidirectional"))
    )
    (net (code "105") (name "unconnected-(ARDUINO-PCINT3_PB3-Pad17)") (class "Default")
      (node (ref "ARDUINO") (pin "17") (pinfunction "PCINT3_PB3_17") (pintype "bidirectional"))
    )
    (net (code "106") (name "unconnected-(ARDUINO-PCINT4_PB4-Pad18)") (class "Default")
      (node (ref "ARDUINO") (pin "18") (pinfunction "PCINT4_PB4_18") (pintype "bidirectional"))
    )
    (net (code "107") (name "unconnected-(MAX7219-DIG5-Pad10)") (class "Default")
      (node (ref "MAX7219") (pin "10") (pinfunction "DIG5_10") (pintype "unspecified"))
    )
    (net (code "108") (name "unconnected-(MAX7219-DIG6-Pad5)") (class "Default")
      (node (ref "MAX7219") (pin "5") (pinfunction "DIG6_5") (pintype "unspecified"))
    )
    (net (code "109") (name "unconnected-(MAX7219-DIG7-Pad8)") (class "Default")
      (node (ref "MAX7219") (pin "8") (pinfunction "DIG7_8") (pintype "unspecified"))
    )
    (net (code "110") (name "unconnected-(MAX7219-DOUT-Pad24)") (class "Default")
      (node (ref "MAX7219") (pin "24") (pinfunction "DOUT_24") (pintype "unspecified"))
    )
    (net (code "111") (name "unconnected-(U2-TAB-Pad4)") (class "Default")
      (node (ref "U2") (pin "4") (pinfunction "TAB_4") (pintype "unspecified"))
    )
    (net (code "112") (name "unconnected-(U5-Q7-Pad7)") (class "Default")
      (node (ref "U5") (pin "7") (pinfunction "Q7_7") (pintype "unspecified"))
    )
    (net (code "113") (name "unconnected-(U6-Q7-Pad7)") (class "Default")
      (node (ref "U6") (pin "7") (pinfunction "Q7_7") (pintype "unspecified"))
    )
    (net (code "114") (name "unconnected-(U7-Q7-Pad7)") (class "Default")
      (node (ref "U7") (pin "7") (pinfunction "Q7_7") (pintype "unspecified"))
    )
    (net (code "115") (name "unconnected-(U8-Q7-Pad7)") (class "Default")
      (node (ref "U8") (pin "7") (pinfunction "Q7_7") (pintype "unspecified"))
    )
    (net (code "116") (name "unconnected-(U9-DS-Pad10)") (class "Default")
      (node (ref "U9") (pin "10") (pinfunction "DS_10") (pintype "unspecified"))
    )
    (net (code "117") (name "unconnected-(U9-Q7-Pad7)") (class "Default")
      (node (ref "U9") (pin "7") (pinfunction "Q7_7") (pintype "unspecified"))
    )
  )
)
